# OperantFEDv3.net
KiCad netlist of a schematic drawn in EAGLE
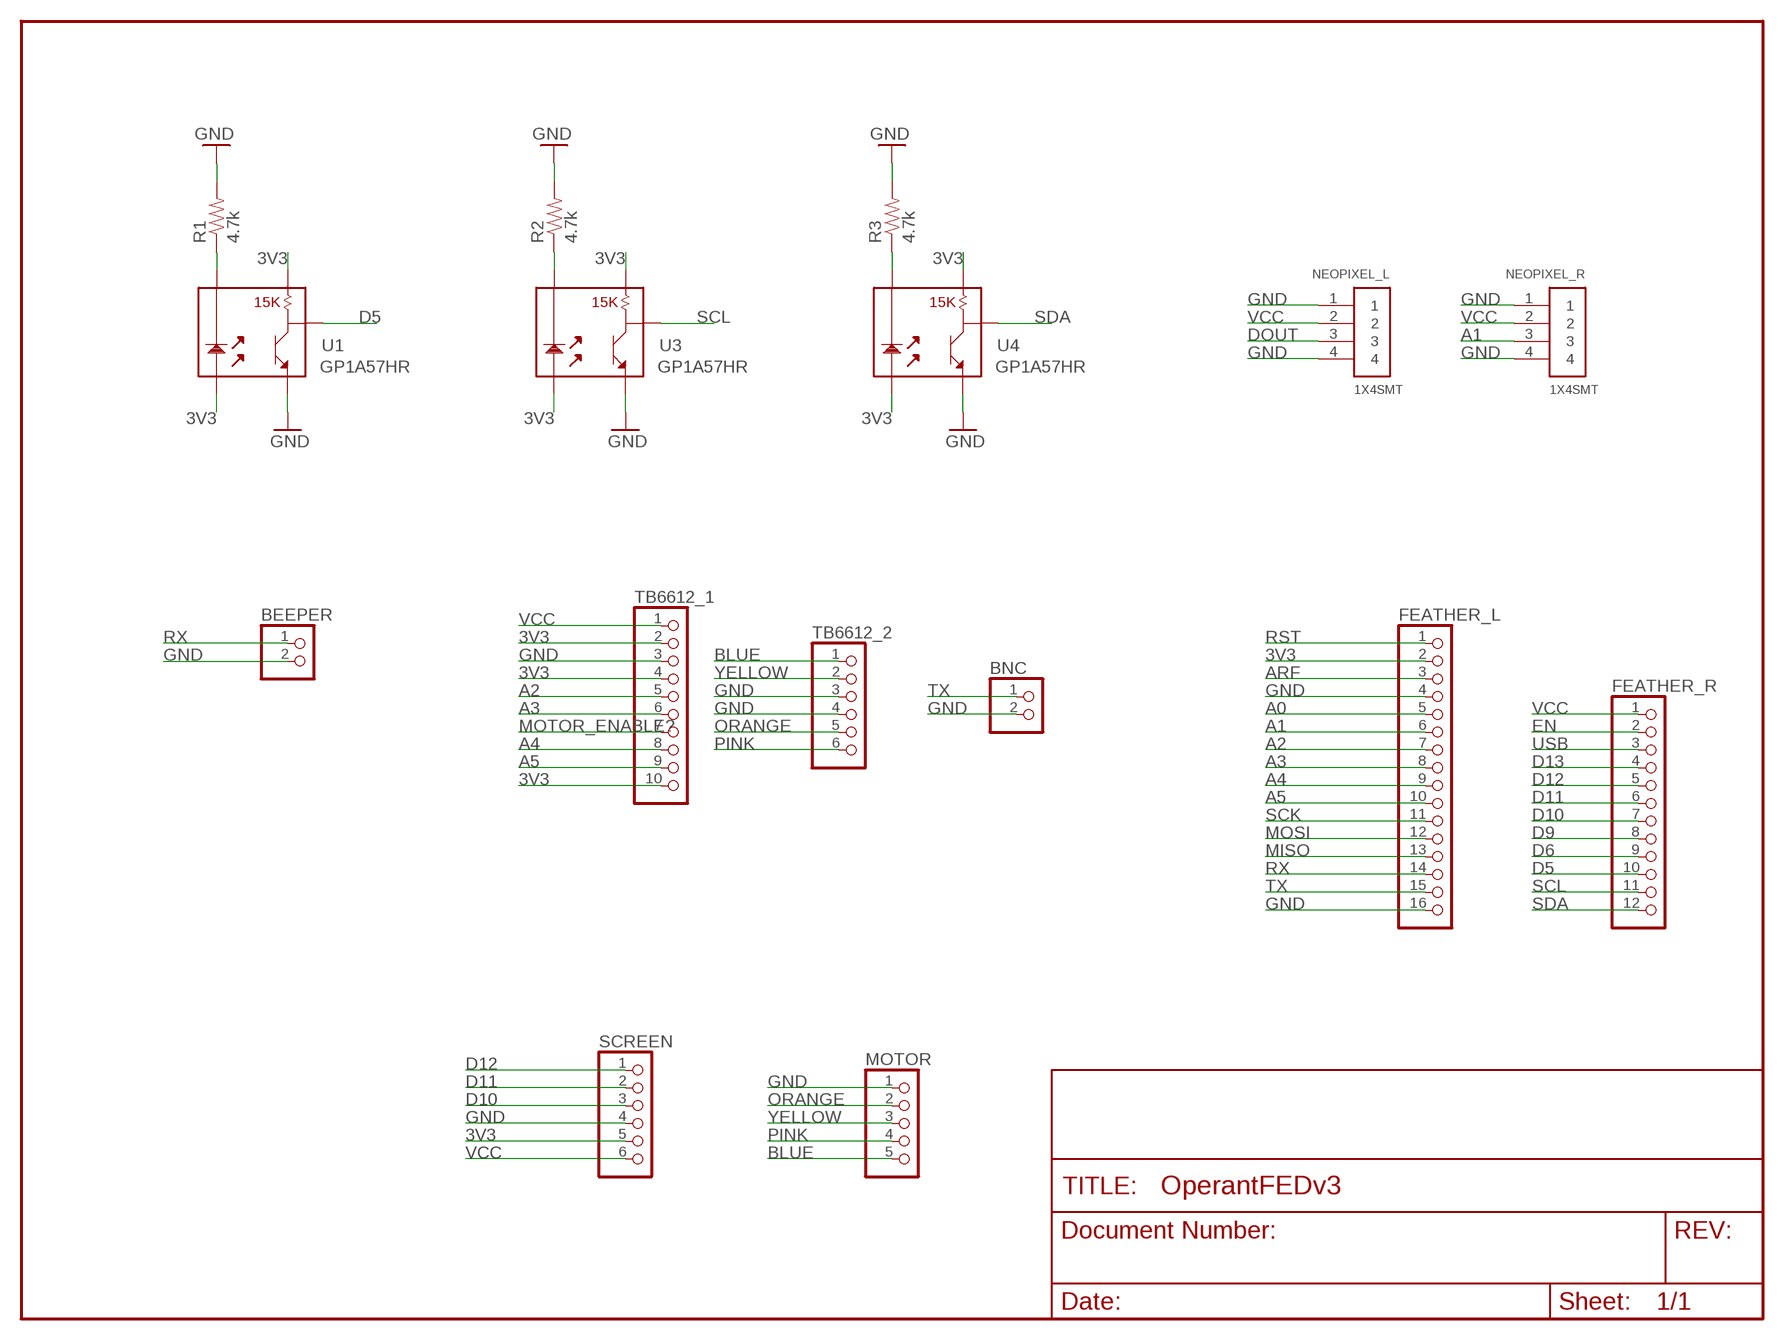
[diagram p0: schematic, sheet 1]

(export (version "E")
  (design (tool "Eeschema 10.0.6"))
  (components
    (comp (ref "BEEPER")
      (value "PINHD-1X2")
      (footprint "eagle-import:1X02")
      (libsource (lib "eagle-import") (part "PINHD-1X2"))
    )
    (comp (ref "BNC")
      (value "PINHD-1X2")
      (footprint "eagle-import:1X02")
      (libsource (lib "eagle-import") (part "PINHD-1X2"))
    )
    (comp (ref "FEATHER_L")
      (value "PINHD-1X16")
      (footprint "eagle-import:1X16")
      (libsource (lib "eagle-import") (part "PINHD-1X16"))
    )
    (comp (ref "FEATHER_R")
      (value "PINHD-1X12")
      (footprint "eagle-import:1X12")
      (libsource (lib "eagle-import") (part "PINHD-1X12"))
    )
    (comp (ref "MOTOR")
      (value "PINHD-1X5")
      (footprint "eagle-import:1X05")
      (libsource (lib "eagle-import") (part "PINHD-1X5"))
    )
    (comp (ref "NEOPIXEL_L")
      (value "1X4SMT")
      (footprint "eagle-import:1X4-SMT")
      (libsource (lib "eagle-import") (part "1X4SMT"))
    )
    (comp (ref "NEOPIXEL_R")
      (value "1X4SMT")
      (footprint "eagle-import:1X4-SMT")
      (libsource (lib "eagle-import") (part "1X4SMT"))
    )
    (comp (ref "R1")
      (value "4.7k")
      (footprint "eagle-import:AXIAL-0.3")
      (libsource (lib "eagle-import") (part "RESISTORPTH1"))
    )
    (comp (ref "R2")
      (value "4.7k")
      (footprint "eagle-import:AXIAL-0.3")
      (libsource (lib "eagle-import") (part "RESISTORPTH1"))
    )
    (comp (ref "R3")
      (value "4.7k")
      (footprint "eagle-import:AXIAL-0.3")
      (libsource (lib "eagle-import") (part "RESISTORPTH1"))
    )
    (comp (ref "SCREEN")
      (value "PINHD-1X6")
      (footprint "eagle-import:1X06")
      (libsource (lib "eagle-import") (part "PINHD-1X6"))
    )
    (comp (ref "TB6612_1")
      (value "PINHD-1X10")
      (footprint "eagle-import:1X10")
      (libsource (lib "eagle-import") (part "PINHD-1X10"))
    )
    (comp (ref "TB6612_2")
      (value "PINHD-1X6")
      (footprint "eagle-import:1X06")
      (libsource (lib "eagle-import") (part "PINHD-1X6"))
    )
    (comp (ref "U1")
      (value "GP1A57HR")
      (footprint "eagle-import:GP1A57HR")
      (libsource (lib "eagle-import") (part "GP1A57HR"))
    )
    (comp (ref "U3")
      (value "GP1A57HR")
      (footprint "eagle-import:GP1A57HR")
      (libsource (lib "eagle-import") (part "GP1A57HR"))
    )
    (comp (ref "U4")
      (value "GP1A57HR")
      (footprint "eagle-import:GP1A57HR")
      (libsource (lib "eagle-import") (part "GP1A57HR"))
    )
  )
  (nets
    (net (code "1") (name "/3V3") (class "Default")
      (node (ref "FEATHER_L") (pin "2") (pinfunction "2_2") (pintype "passive"))
      (node (ref "SCREEN") (pin "5") (pinfunction "5_5") (pintype "passive"))
      (node (ref "TB6612_1") (pin "10") (pinfunction "10_10") (pintype "passive"))
      (node (ref "TB6612_1") (pin "2") (pinfunction "2_2") (pintype "passive"))
      (node (ref "TB6612_1") (pin "4") (pinfunction "4_4") (pintype "passive"))
      (node (ref "U1") (pin "1") (pinfunction "1_1") (pintype "bidirectional"))
      (node (ref "U1") (pin "3") (pinfunction "3_3") (pintype "bidirectional"))
      (node (ref "U3") (pin "1") (pinfunction "1_1") (pintype "bidirectional"))
      (node (ref "U3") (pin "3") (pinfunction "3_3") (pintype "bidirectional"))
      (node (ref "U4") (pin "1") (pinfunction "1_1") (pintype "bidirectional"))
      (node (ref "U4") (pin "3") (pinfunction "3_3") (pintype "bidirectional"))
    )
    (net (code "2") (name "/A0") (class "Default")
      (node (ref "FEATHER_L") (pin "5") (pinfunction "5_5") (pintype "passive"))
    )
    (net (code "3") (name "/A1") (class "Default")
      (node (ref "FEATHER_L") (pin "6") (pinfunction "6_6") (pintype "passive"))
      (node (ref "NEOPIXEL_R") (pin "3") (pinfunction "3_3") (pintype "bidirectional"))
    )
    (net (code "4") (name "/A2") (class "Default")
      (node (ref "FEATHER_L") (pin "7") (pinfunction "7_7") (pintype "passive"))
      (node (ref "TB6612_1") (pin "5") (pinfunction "5_5") (pintype "passive"))
    )
    (net (code "5") (name "/A3") (class "Default")
      (node (ref "FEATHER_L") (pin "8") (pinfunction "8_8") (pintype "passive"))
      (node (ref "TB6612_1") (pin "6") (pinfunction "6_6") (pintype "passive"))
    )
    (net (code "6") (name "/A4") (class "Default")
      (node (ref "FEATHER_L") (pin "9") (pinfunction "9_9") (pintype "passive"))
      (node (ref "TB6612_1") (pin "8") (pinfunction "8_8") (pintype "passive"))
    )
    (net (code "7") (name "/A5") (class "Default")
      (node (ref "FEATHER_L") (pin "10") (pinfunction "10_10") (pintype "passive"))
      (node (ref "TB6612_1") (pin "9") (pinfunction "9_9") (pintype "passive"))
    )
    (net (code "8") (name "/ARF") (class "Default")
      (node (ref "FEATHER_L") (pin "3") (pinfunction "3_3") (pintype "passive"))
    )
    (net (code "9") (name "/BLUE") (class "Default")
      (node (ref "MOTOR") (pin "5") (pinfunction "5_5") (pintype "passive"))
      (node (ref "TB6612_2") (pin "1") (pinfunction "1_1") (pintype "passive"))
    )
    (net (code "10") (name "/D5") (class "Default")
      (node (ref "FEATHER_R") (pin "10") (pinfunction "10_10") (pintype "passive"))
      (node (ref "U1") (pin "4") (pinfunction "4_4") (pintype "bidirectional"))
    )
    (net (code "11") (name "/D6") (class "Default")
      (node (ref "FEATHER_R") (pin "9") (pinfunction "9_9") (pintype "passive"))
    )
    (net (code "12") (name "/D9") (class "Default")
      (node (ref "FEATHER_R") (pin "8") (pinfunction "8_8") (pintype "passive"))
    )
    (net (code "13") (name "/D10") (class "Default")
      (node (ref "FEATHER_R") (pin "7") (pinfunction "7_7") (pintype "passive"))
      (node (ref "SCREEN") (pin "3") (pinfunction "3_3") (pintype "passive"))
    )
    (net (code "14") (name "/D11") (class "Default")
      (node (ref "FEATHER_R") (pin "6") (pinfunction "6_6") (pintype "passive"))
      (node (ref "SCREEN") (pin "2") (pinfunction "2_2") (pintype "passive"))
    )
    (net (code "15") (name "/D12") (class "Default")
      (node (ref "FEATHER_R") (pin "5") (pinfunction "5_5") (pintype "passive"))
      (node (ref "SCREEN") (pin "1") (pinfunction "1_1") (pintype "passive"))
    )
    (net (code "16") (name "/D13") (class "Default")
      (node (ref "FEATHER_R") (pin "4") (pinfunction "4_4") (pintype "passive"))
    )
    (net (code "17") (name "/DOUT") (class "Default")
      (node (ref "NEOPIXEL_L") (pin "3") (pinfunction "3_3") (pintype "bidirectional"))
    )
    (net (code "18") (name "/EN") (class "Default")
      (node (ref "FEATHER_R") (pin "2") (pinfunction "2_2") (pintype "passive"))
    )
    (net (code "19") (name "/MISO") (class "Default")
      (node (ref "FEATHER_L") (pin "13") (pinfunction "13_13") (pintype "passive"))
    )
    (net (code "20") (name "/MOSI") (class "Default")
      (node (ref "FEATHER_L") (pin "12") (pinfunction "12_12") (pintype "passive"))
    )
    (net (code "21") (name "/MOTOR_ENABLE?") (class "Default")
      (node (ref "TB6612_1") (pin "7") (pinfunction "7_7") (pintype "passive"))
    )
    (net (code "22") (name "/ORANGE") (class "Default")
      (node (ref "MOTOR") (pin "2") (pinfunction "2_2") (pintype "passive"))
      (node (ref "TB6612_2") (pin "5") (pinfunction "5_5") (pintype "passive"))
    )
    (net (code "23") (name "/PINK") (class "Default")
      (node (ref "MOTOR") (pin "4") (pinfunction "4_4") (pintype "passive"))
      (node (ref "TB6612_2") (pin "6") (pinfunction "6_6") (pintype "passive"))
    )
    (net (code "24") (name "/RST") (class "Default")
      (node (ref "FEATHER_L") (pin "1") (pinfunction "1_1") (pintype "passive"))
    )
    (net (code "25") (name "/RX") (class "Default")
      (node (ref "BEEPER") (pin "1") (pinfunction "1_1") (pintype "passive"))
      (node (ref "FEATHER_L") (pin "14") (pinfunction "14_14") (pintype "passive"))
    )
    (net (code "26") (name "/SCK") (class "Default")
      (node (ref "FEATHER_L") (pin "11") (pinfunction "11_11") (pintype "passive"))
    )
    (net (code "27") (name "/SCL") (class "Default")
      (node (ref "FEATHER_R") (pin "11") (pinfunction "11_11") (pintype "passive"))
      (node (ref "U3") (pin "4") (pinfunction "4_4") (pintype "bidirectional"))
    )
    (net (code "28") (name "/SDA") (class "Default")
      (node (ref "FEATHER_R") (pin "12") (pinfunction "12_12") (pintype "passive"))
      (node (ref "U4") (pin "4") (pinfunction "4_4") (pintype "bidirectional"))
    )
    (net (code "29") (name "/TX") (class "Default")
      (node (ref "BNC") (pin "1") (pinfunction "1_1") (pintype "passive"))
      (node (ref "FEATHER_L") (pin "15") (pinfunction "15_15") (pintype "passive"))
    )
    (net (code "30") (name "/USB") (class "Default")
      (node (ref "FEATHER_R") (pin "3") (pinfunction "3_3") (pintype "passive"))
    )
    (net (code "31") (name "/VCC") (class "Default")
      (node (ref "FEATHER_R") (pin "1") (pinfunction "1_1") (pintype "passive"))
      (node (ref "NEOPIXEL_L") (pin "2") (pinfunction "2_2") (pintype "bidirectional"))
      (node (ref "NEOPIXEL_R") (pin "2") (pinfunction "2_2") (pintype "bidirectional"))
      (node (ref "SCREEN") (pin "6") (pinfunction "6_6") (pintype "passive"))
      (node (ref "TB6612_1") (pin "1") (pinfunction "1_1") (pintype "passive"))
    )
    (net (code "32") (name "/YELLOW") (class "Default")
      (node (ref "MOTOR") (pin "3") (pinfunction "3_3") (pintype "passive"))
      (node (ref "TB6612_2") (pin "2") (pinfunction "2_2") (pintype "passive"))
    )
    (net (code "33") (name "GND") (class "Default")
      (node (ref "BEEPER") (pin "2") (pinfunction "2_2") (pintype "passive"))
      (node (ref "BNC") (pin "2") (pinfunction "2_2") (pintype "passive"))
      (node (ref "FEATHER_L") (pin "16") (pinfunction "16_16") (pintype "passive"))
      (node (ref "FEATHER_L") (pin "4") (pinfunction "4_4") (pintype "passive"))
      (node (ref "MOTOR") (pin "1") (pinfunction "1_1") (pintype "passive"))
      (node (ref "NEOPIXEL_L") (pin "1") (pinfunction "1_1") (pintype "bidirectional"))
      (node (ref "NEOPIXEL_L") (pin "4") (pinfunction "4_4") (pintype "bidirectional"))
      (node (ref "NEOPIXEL_R") (pin "1") (pinfunction "1_1") (pintype "bidirectional"))
      (node (ref "NEOPIXEL_R") (pin "4") (pinfunction "4_4") (pintype "bidirectional"))
      (node (ref "R1") (pin "P$2") (pinfunction "2_P$2") (pintype "passive"))
      (node (ref "R2") (pin "P$2") (pinfunction "2_P$2") (pintype "passive"))
      (node (ref "R3") (pin "P$2") (pinfunction "2_P$2") (pintype "passive"))
      (node (ref "SCREEN") (pin "4") (pinfunction "4_4") (pintype "passive"))
      (node (ref "TB6612_1") (pin "3") (pinfunction "3_3") (pintype "passive"))
      (node (ref "TB6612_2") (pin "3") (pinfunction "3_3") (pintype "passive"))
      (node (ref "TB6612_2") (pin "4") (pinfunction "4_4") (pintype "passive"))
      (node (ref "U1") (pin "5") (pinfunction "5_5") (pintype "bidirectional"))
      (node (ref "U3") (pin "5") (pinfunction "5_5") (pintype "bidirectional"))
      (node (ref "U4") (pin "5") (pinfunction "5_5") (pintype "bidirectional"))
    )
    (net (code "34") (name "Net-(R1-1)") (class "Default")
      (node (ref "R1") (pin "P$1") (pinfunction "1_P$1") (pintype "passive"))
      (node (ref "U1") (pin "2") (pinfunction "2_2") (pintype "bidirectional"))
    )
    (net (code "35") (name "Net-(R2-1)") (class "Default")
      (node (ref "R2") (pin "P$1") (pinfunction "1_P$1") (pintype "passive"))
      (node (ref "U3") (pin "2") (pinfunction "2_2") (pintype "bidirectional"))
    )
    (net (code "36") (name "Net-(R3-1)") (class "Default")
      (node (ref "R3") (pin "P$1") (pinfunction "1_P$1") (pintype "passive"))
      (node (ref "U4") (pin "2") (pinfunction "2_2") (pintype "bidirectional"))
    )
  )
)
